# CP2102.net
KiCad netlist of a schematic drawn in Altium Designer
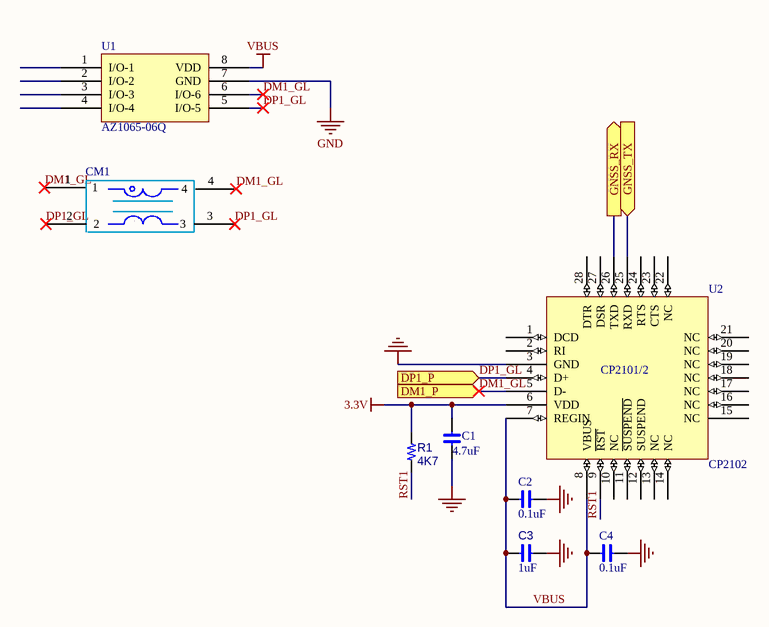
[diagram p0: CP2102.SchDoc]

(export (version "E")
  (design (tool "Eeschema 10.0.6"))
  (components
    (comp (ref "C1")
      (value "C")
      (footprint "0603CAPC1608X09N")
      (fields (field (name "ALTIUM_UNNAMED_1") "4.7uF"))
      (libsource (lib "Schlib_20130601") (part "C"))
    )
    (comp (ref "C2")
      (value "C")
      (footprint "0402CAPC1005X06N")
      (fields (field (name "ALTIUM_UNNAMED_1") "0.1uF"))
      (libsource (lib "Schlib_20130601") (part "C"))
    )
    (comp (ref "C3")
      (value "15pF")
      (footprint "0402CAPC1005X06N")
      (description "C")
      (fields (field (name "ALTIUM_UNNAMED_1") "1uF"))
      (libsource (lib "Schlib_20130101") (part "C"))
    )
    (comp (ref "C4")
      (value "C")
      (footprint "0402CAPC1005X06N")
      (fields (field (name "ALTIUM_UNNAMED_1") "0.1uF"))
      (libsource (lib "Schlib_20130601") (part "C"))
    )
    (comp (ref "CM1")
      (value "CM")
      (footprint "SMD_4P")
      (description "USB Comon Choke")
      (libsource (lib "Schlib_20130601") (part "CM"))
    )
    (comp (ref "R1")
      (value "4K7")
      (footprint "0402RESC1005X04N")
      (description "R")
      (libsource (lib "Schlib_20130101") (part "R"))
    )
    (comp (ref "U1")
      (value "AZ1065-06Q")
      (footprint "MSOP-8")
      (libsource (lib "Schlib_20130601") (part "AZ1065-06Q"))
    )
    (comp (ref "U2")
      (value "CP2102")
      (footprint "QFN-28")
      (libsource (lib "Schlib_20130601") (part "CP2101/2"))
    )
  )
  (nets
    (net (code "1") (name "/DM1_GL") (class "Default")
      (node (ref "CM1") (pin "1") (pinfunction "1_1") (pintype "passive"))
      (node (ref "CM1") (pin "4") (pinfunction "4_4") (pintype "passive"))
      (node (ref "U1") (pin "6") (pinfunction "I/O-6_6") (pintype "passive"))
      (node (ref "U2") (pin "5") (pinfunction "D-_5") (pintype "power_in"))
    )
    (net (code "2") (name "/DP1_GL") (class "Default")
      (node (ref "CM1") (pin "2") (pinfunction "2_2") (pintype "passive"))
      (node (ref "CM1") (pin "3") (pinfunction "3_3") (pintype "passive"))
      (node (ref "U1") (pin "5") (pinfunction "I/O-5_5") (pintype "passive"))
      (node (ref "U2") (pin "4") (pinfunction "D+_4") (pintype "bidirectional"))
    )
    (net (code "3") (name "/GNSS_RX") (class "Default")
      (node (ref "U2") (pin "26") (pinfunction "TXD_26") (pintype "bidirectional"))
    )
    (net (code "4") (name "/GNSS_TX") (class "Default")
      (node (ref "U2") (pin "25") (pinfunction "RXD_25") (pintype "bidirectional"))
    )
    (net (code "5") (name "/RST1") (class "Default")
      (node (ref "R1") (pin "2") (pintype "passive"))
      (node (ref "U2") (pin "9") (pinfunction "~{RST}_9") (pintype "bidirectional"))
    )
    (net (code "6") (name "3.3V") (class "Default")
      (node (ref "C1") (pin "2") (pintype "passive"))
      (node (ref "R1") (pin "1") (pintype "passive"))
      (node (ref "U2") (pin "6") (pinfunction "VDD_6") (pintype "power_in"))
    )
    (net (code "7") (name "GND") (class "Default")
      (node (ref "C1") (pin "1") (pintype "passive"))
      (node (ref "C2") (pin "1") (pintype "passive"))
      (node (ref "C3") (pin "2") (pintype "passive"))
      (node (ref "C4") (pin "1") (pintype "passive"))
      (node (ref "U1") (pin "7") (pinfunction "GND_7") (pintype "passive"))
      (node (ref "U2") (pin "3") (pinfunction "GND_3") (pintype "power_in"))
    )
    (net (code "8") (name "VBUS") (class "Default")
      (node (ref "C2") (pin "2") (pintype "passive"))
      (node (ref "C3") (pin "1") (pintype "passive"))
      (node (ref "C4") (pin "2") (pintype "passive"))
      (node (ref "U1") (pin "8") (pinfunction "VDD_8") (pintype "passive"))
      (node (ref "U2") (pin "7") (pinfunction "REGIN_7") (pintype "bidirectional"))
      (node (ref "U2") (pin "8") (pinfunction "VBUS_8") (pintype "bidirectional"))
    )
    (net (code "9") (name "unconnected-(U1-I{slash}O-1-Pad1)") (class "Default")
      (node (ref "U1") (pin "1") (pinfunction "I/O-1_1") (pintype "passive"))
    )
    (net (code "10") (name "unconnected-(U1-I{slash}O-2-Pad2)") (class "Default")
      (node (ref "U1") (pin "2") (pinfunction "I/O-2_2") (pintype "passive"))
    )
    (net (code "11") (name "unconnected-(U1-I{slash}O-3-Pad3)") (class "Default")
      (node (ref "U1") (pin "3") (pinfunction "I/O-3_3") (pintype "passive"))
    )
    (net (code "12") (name "unconnected-(U1-I{slash}O-4-Pad4)") (class "Default")
      (node (ref "U1") (pin "4") (pinfunction "I/O-4_4") (pintype "passive"))
    )
    (net (code "13") (name "unconnected-(U2-CTS-Pad23)") (class "Default")
      (node (ref "U2") (pin "23") (pinfunction "CTS_23") (pintype "bidirectional"))
    )
    (net (code "14") (name "unconnected-(U2-DCD-Pad1)") (class "Default")
      (node (ref "U2") (pin "1") (pinfunction "DCD_1") (pintype "bidirectional"))
    )
    (net (code "15") (name "unconnected-(U2-DSR-Pad27)") (class "Default")
      (node (ref "U2") (pin "27") (pinfunction "DSR_27") (pintype "bidirectional"))
    )
    (net (code "16") (name "unconnected-(U2-DTR-Pad28)") (class "Default")
      (node (ref "U2") (pin "28") (pinfunction "DTR_28") (pintype "bidirectional"))
    )
    (net (code "17") (name "unconnected-(U2-NC-Pad10)") (class "Default")
      (node (ref "U2") (pin "10") (pinfunction "NC_10") (pintype "bidirectional"))
    )
    (net (code "18") (name "unconnected-(U2-NC-Pad13)") (class "Default")
      (node (ref "U2") (pin "13") (pinfunction "NC_13") (pintype "bidirectional"))
    )
    (net (code "19") (name "unconnected-(U2-NC-Pad14)") (class "Default")
      (node (ref "U2") (pin "14") (pinfunction "NC_14") (pintype "bidirectional"))
    )
    (net (code "20") (name "unconnected-(U2-NC-Pad15)") (class "Default")
      (node (ref "U2") (pin "15") (pinfunction "NC_15") (pintype "power_in"))
    )
    (net (code "21") (name "unconnected-(U2-NC-Pad16)") (class "Default")
      (node (ref "U2") (pin "16") (pinfunction "NC_16") (pintype "bidirectional"))
    )
    (net (code "22") (name "unconnected-(U2-NC-Pad17)") (class "Default")
      (node (ref "U2") (pin "17") (pinfunction "NC_17") (pintype "bidirectional"))
    )
    (net (code "23") (name "unconnected-(U2-NC-Pad18)") (class "Default")
      (node (ref "U2") (pin "18") (pinfunction "NC_18") (pintype "bidirectional"))
    )
    (net (code "24") (name "unconnected-(U2-NC-Pad19)") (class "Default")
      (node (ref "U2") (pin "19") (pinfunction "NC_19") (pintype "bidirectional"))
    )
    (net (code "25") (name "unconnected-(U2-NC-Pad20)") (class "Default")
      (node (ref "U2") (pin "20") (pinfunction "NC_20") (pintype "bidirectional"))
    )
    (net (code "26") (name "unconnected-(U2-NC-Pad21)") (class "Default")
      (node (ref "U2") (pin "21") (pinfunction "NC_21") (pintype "bidirectional"))
    )
    (net (code "27") (name "unconnected-(U2-NC-Pad22)") (class "Default")
      (node (ref "U2") (pin "22") (pinfunction "NC_22") (pintype "bidirectional"))
    )
    (net (code "28") (name "unconnected-(U2-RI-Pad2)") (class "Default")
      (node (ref "U2") (pin "2") (pinfunction "RI_2") (pintype "bidirectional"))
    )
    (net (code "29") (name "unconnected-(U2-RTS-Pad24)") (class "Default")
      (node (ref "U2") (pin "24") (pinfunction "RTS_24") (pintype "bidirectional"))
    )
    (net (code "30") (name "unconnected-(U2-SUSPEND-Pad12)") (class "Default")
      (node (ref "U2") (pin "12") (pinfunction "SUSPEND_12") (pintype "bidirectional"))
    )
    (net (code "31") (name "unconnected-(U2-~{SUSPEND}-Pad11)") (class "Default")
      (node (ref "U2") (pin "11") (pinfunction "~{SUSPEND}_11") (pintype "bidirectional"))
    )
  )
)
